# CO2-Ampel_v10.net
KiCad netlist of a schematic drawn in EAGLE
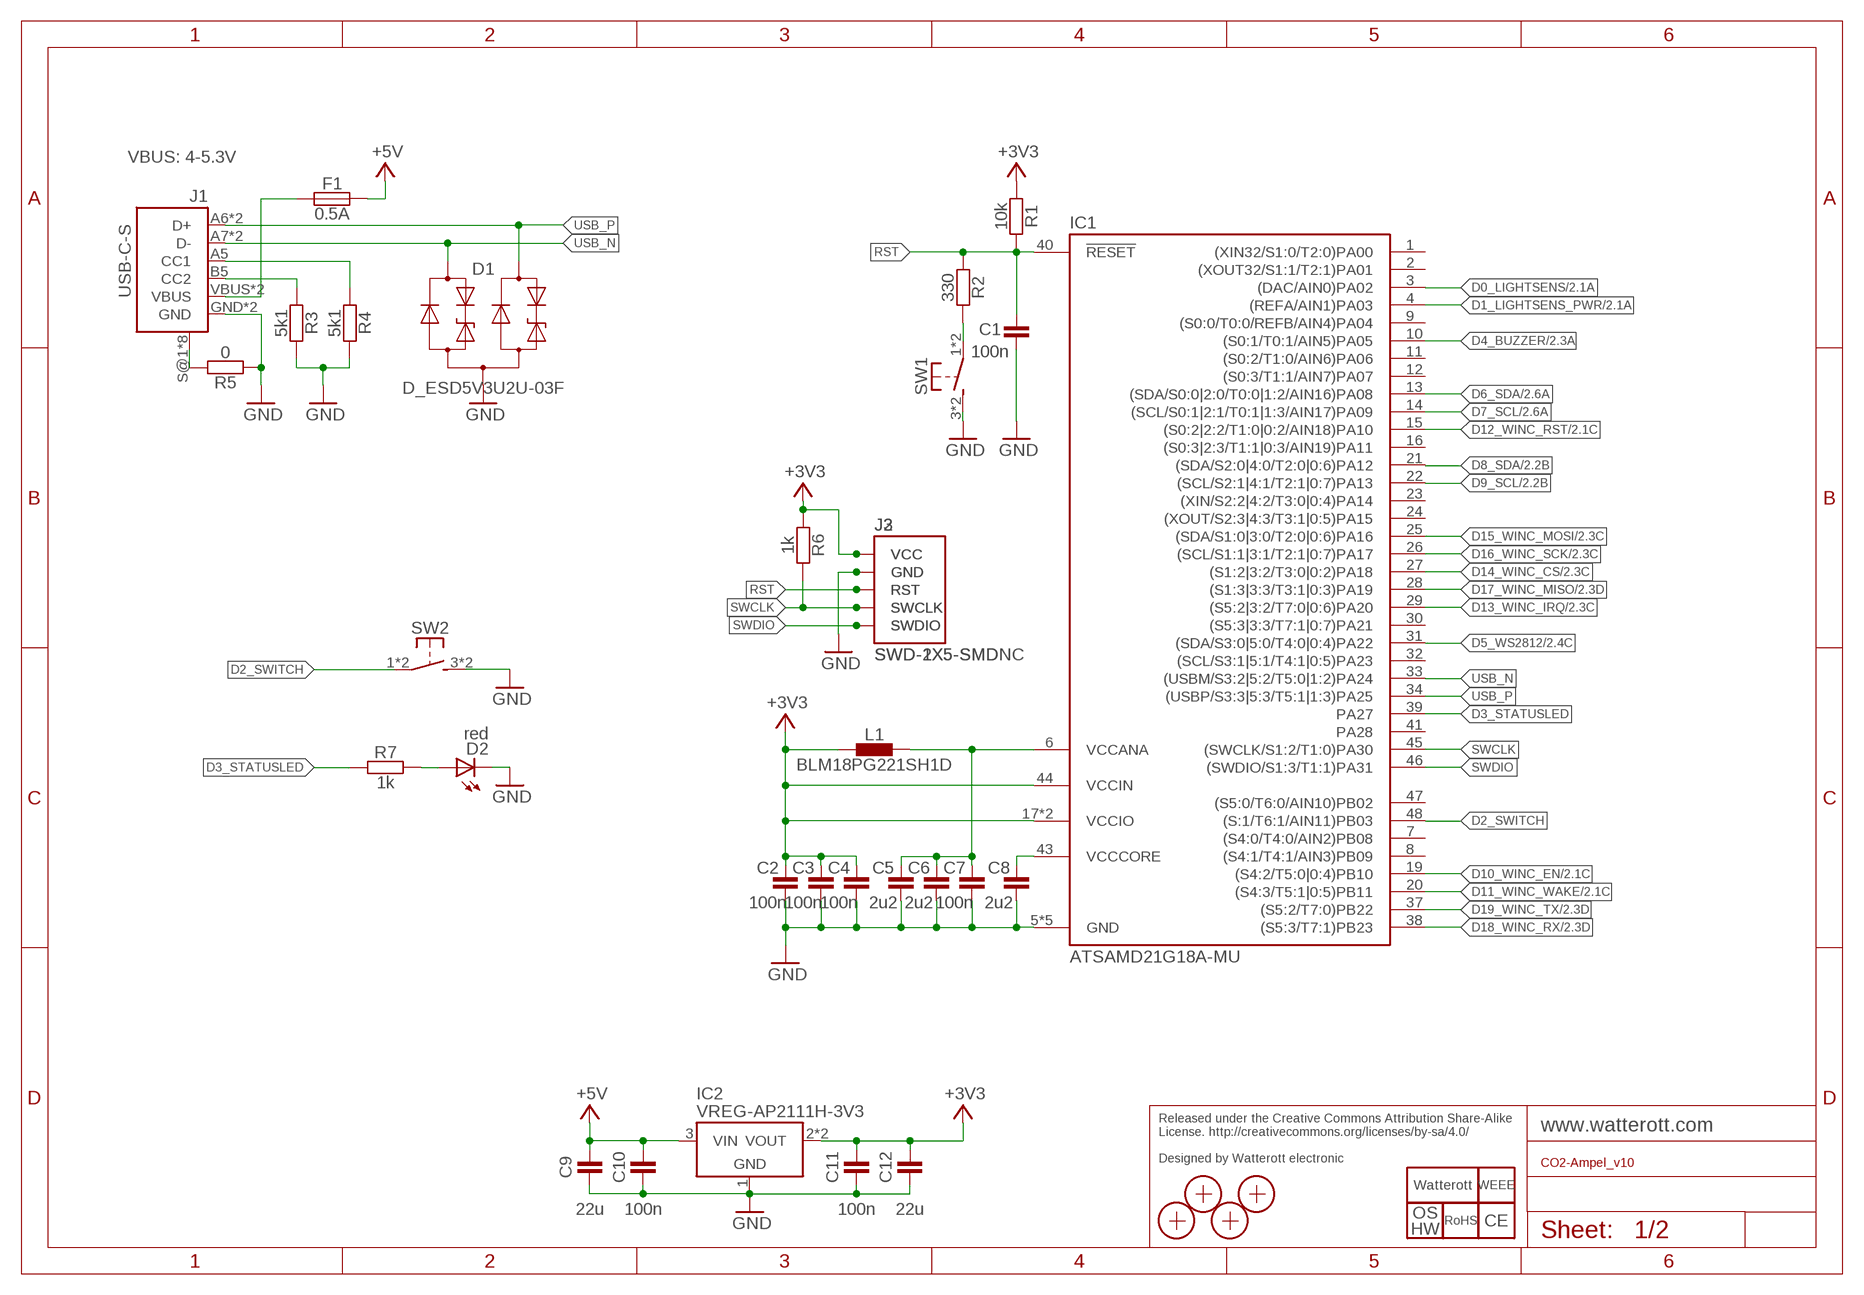
[diagram p0: schematic, sheet 1]
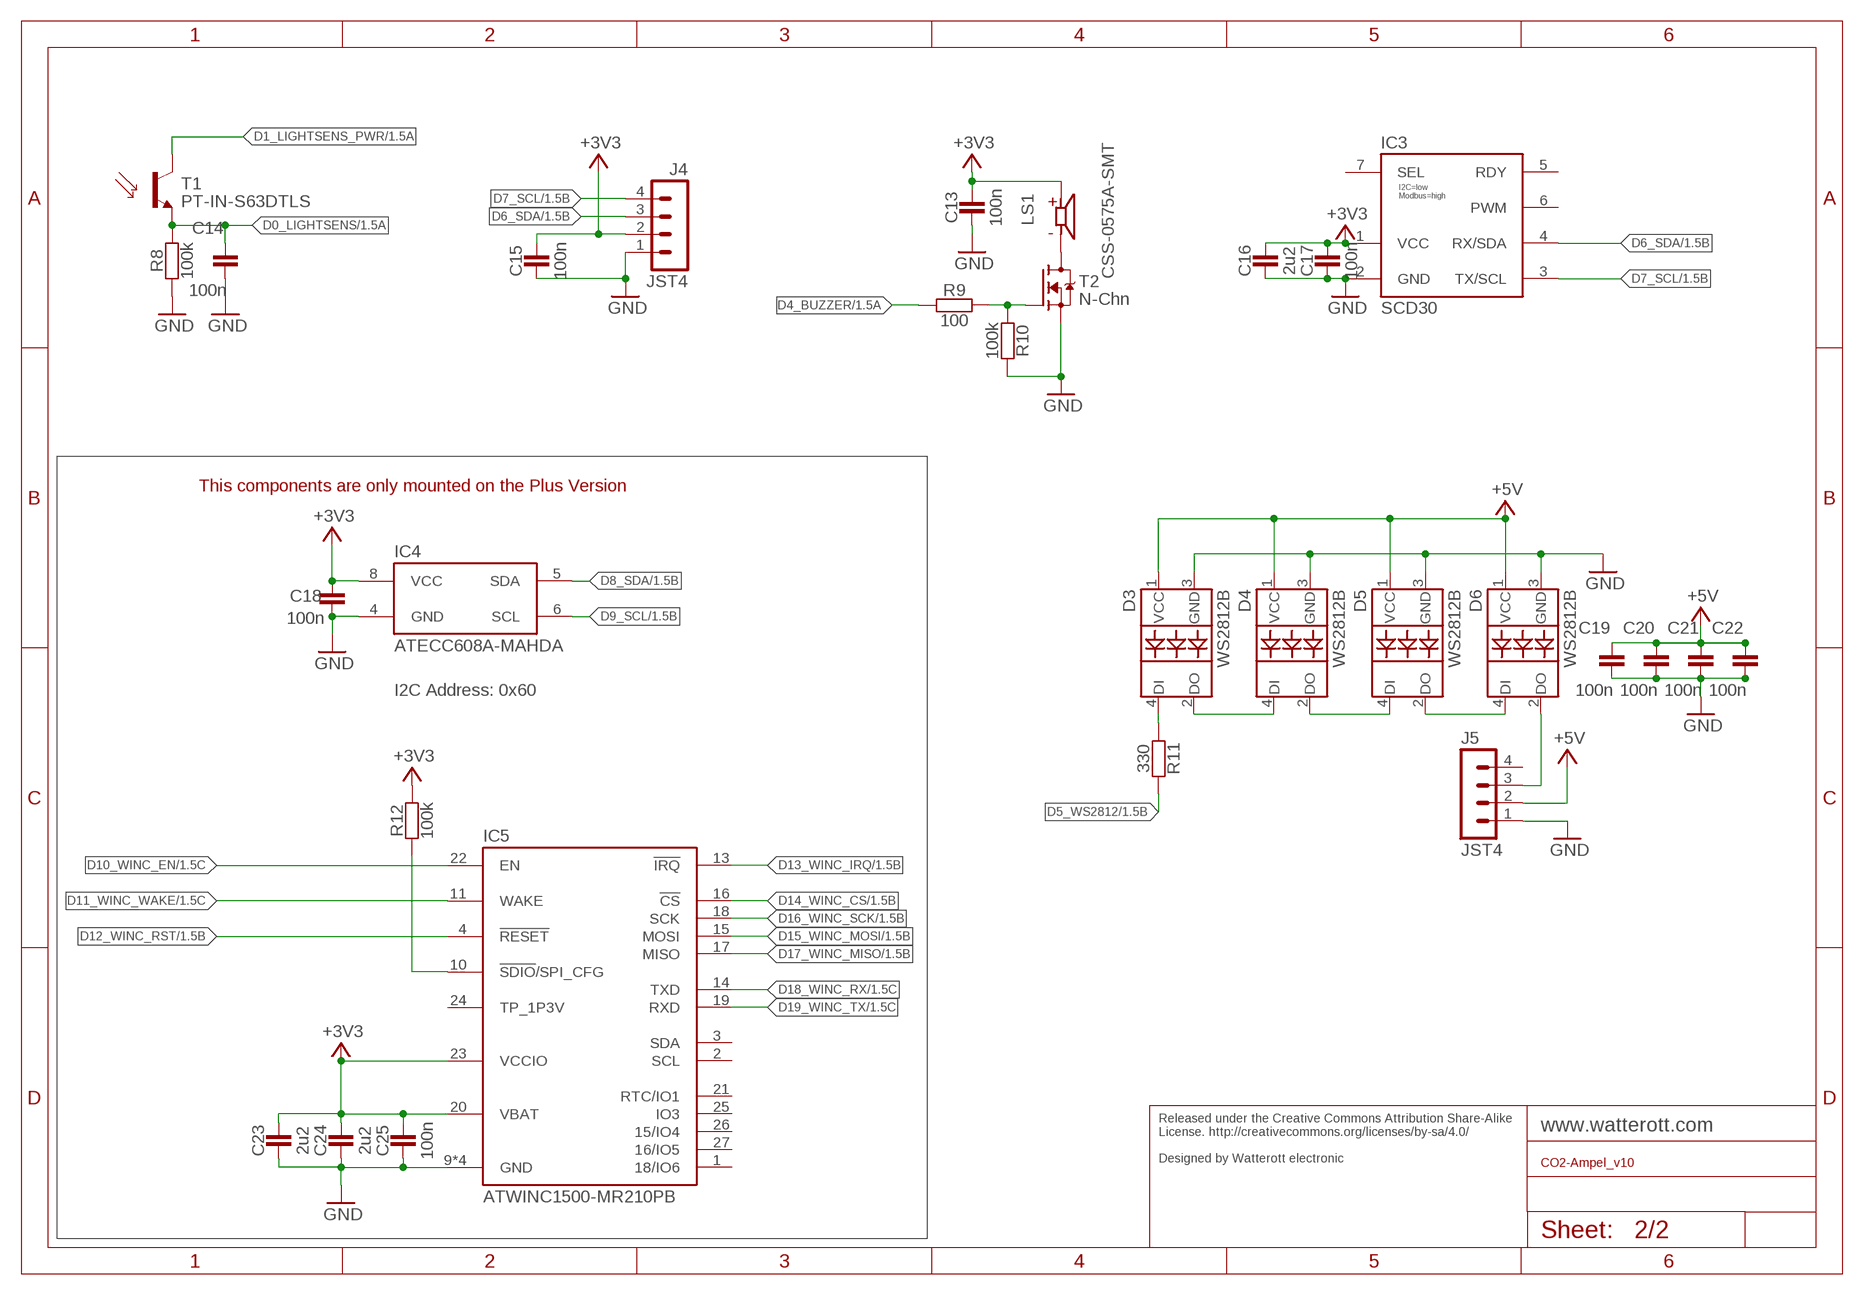
[diagram p1: schematic, sheet 2]

(export (version "E")
  (design (tool "Eeschema 10.0.6"))
  (components
    (comp (ref "C1")
      (value "100n")
      (footprint "eagle-import:C0402")
      (libsource (lib "eagle-import") (part "CAPACITOR-0402"))
    )
    (comp (ref "C2")
      (value "100n")
      (footprint "eagle-import:C0402")
      (libsource (lib "eagle-import") (part "CAPACITOR-0402"))
    )
    (comp (ref "C3")
      (value "100n")
      (footprint "eagle-import:C0402")
      (libsource (lib "eagle-import") (part "CAPACITOR-0402"))
    )
    (comp (ref "C4")
      (value "100n")
      (footprint "eagle-import:C0402")
      (libsource (lib "eagle-import") (part "CAPACITOR-0402"))
    )
    (comp (ref "C5")
      (value "2u2")
      (footprint "eagle-import:C0402")
      (libsource (lib "eagle-import") (part "CAPACITOR-0402"))
    )
    (comp (ref "C6")
      (value "2u2")
      (footprint "eagle-import:C0402")
      (libsource (lib "eagle-import") (part "CAPACITOR-0402"))
    )
    (comp (ref "C7")
      (value "100n")
      (footprint "eagle-import:C0402")
      (libsource (lib "eagle-import") (part "CAPACITOR-0402"))
    )
    (comp (ref "C8")
      (value "2u2")
      (footprint "eagle-import:C0402")
      (libsource (lib "eagle-import") (part "CAPACITOR-0402"))
    )
    (comp (ref "C9")
      (value "22u")
      (footprint "eagle-import:C0805")
      (libsource (lib "eagle-import") (part "CAPACITOR-0805"))
    )
    (comp (ref "C10")
      (value "100n")
      (footprint "eagle-import:C0402")
      (libsource (lib "eagle-import") (part "CAPACITOR-0402"))
    )
    (comp (ref "C11")
      (value "100n")
      (footprint "eagle-import:C0402")
      (libsource (lib "eagle-import") (part "CAPACITOR-0402"))
    )
    (comp (ref "C12")
      (value "22u")
      (footprint "eagle-import:C0805")
      (libsource (lib "eagle-import") (part "CAPACITOR-0805"))
    )
    (comp (ref "D1")
      (value "D_ESD5V3U2U-03F")
      (footprint "eagle-import:SOT723")
      (libsource (lib "eagle-import") (part "D_ESD5V3U2U-03F"))
    )
    (comp (ref "D2")
      (value "red")
      (footprint "eagle-import:C0603")
      (libsource (lib "eagle-import") (part "LED-0603"))
    )
    (comp (ref "F1")
      (value "0.5A")
      (footprint "eagle-import:C0805")
      (libsource (lib "eagle-import") (part "FUSE-0805"))
    )
    (comp (ref "IC1")
      (value "ATSAMD21G18A-MU")
      (footprint "eagle-import:QFN48-PAD")
      (libsource (lib "eagle-import") (part "ATSAMD21G18A-MU"))
    )
    (comp (ref "IC2")
      (value "VREG-AP2111H-3V3")
      (footprint "eagle-import:SOT223")
      (libsource (lib "eagle-import") (part "VREG-TS1117CW-3V3"))
    )
    (comp (ref "J1")
      (value "USB-C-S")
      (footprint "eagle-import:USB-C-S")
      (libsource (lib "eagle-import") (part "USB-C-S"))
    )
    (comp (ref "J2")
      (value "SWD-2X5-SMD")
      (footprint "eagle-import:SWD-2X5_SMD")
      (libsource (lib "eagle-import") (part "SWD-2X5-SMD"))
    )
    (comp (ref "J3")
      (value "SWD-1X5-SMDNC")
      (footprint "eagle-import:SWD-1X5_SMDNC")
      (libsource (lib "eagle-import") (part "SWD-1X5-SMDNC"))
    )
    (comp (ref "L1")
      (value "BLM18PG221SH1D")
      (footprint "eagle-import:C0603")
      (libsource (lib "eagle-import") (part "INDUCTOR-0603"))
    )
    (comp (ref "LOGO1")
      (value "LOGO_SPARK-4")
      (footprint "eagle-import:SPARK_4MM")
      (libsource (lib "eagle-import") (part "LOGO_SPARK-4"))
    )
    (comp (ref "LOGO2")
      (value "LOGO_WEEE-4")
      (footprint "eagle-import:WEEE_4MM")
      (libsource (lib "eagle-import") (part "LOGO_WEEE-4"))
    )
    (comp (ref "LOGO3")
      (value "OSHW_LOGOX0070")
      (footprint "eagle-import:OSHW_3MM")
      (libsource (lib "eagle-import") (part "LOGO_OSHW-3"))
    )
    (comp (ref "LOGO4")
      (value "LOGO_ROHS-4")
      (footprint "eagle-import:ROHS_4MM")
      (libsource (lib "eagle-import") (part "LOGO_ROHS-4"))
    )
    (comp (ref "LOGO5")
      (value "LOGO_CE-4")
      (footprint "eagle-import:CE_4MM")
      (libsource (lib "eagle-import") (part "LOGO_CE-4"))
    )
    (comp (ref "R1")
      (value "10k")
      (footprint "eagle-import:C0402")
      (libsource (lib "eagle-import") (part "RESISTOR-0402"))
    )
    (comp (ref "R2")
      (value "330")
      (footprint "eagle-import:C0402")
      (libsource (lib "eagle-import") (part "RESISTOR-0402"))
    )
    (comp (ref "R3")
      (value "5k1")
      (footprint "eagle-import:C0402")
      (libsource (lib "eagle-import") (part "RESISTOR-0402"))
    )
    (comp (ref "R4")
      (value "5k1")
      (footprint "eagle-import:C0402")
      (libsource (lib "eagle-import") (part "RESISTOR-0402"))
    )
    (comp (ref "R5")
      (value "0")
      (footprint "eagle-import:C0603")
      (libsource (lib "eagle-import") (part "RESISTOR-0603"))
    )
    (comp (ref "R6")
      (value "1k")
      (footprint "eagle-import:C0402")
      (libsource (lib "eagle-import") (part "RESISTOR-0402"))
    )
    (comp (ref "R7")
      (value "1k")
      (footprint "eagle-import:C0402")
      (libsource (lib "eagle-import") (part "RESISTOR-0402"))
    )
    (comp (ref "SW1")
      (value "PTS645SK50SMTR92-Red")
      (footprint "eagle-import:PTS840P")
      (libsource (lib "eagle-import") (part "SW-TACTILE-PTS840P"))
    )
    (comp (ref "SW2")
      (value "PTS645SH50SMTR92-Grey")
      (footprint "eagle-import:PTS840P")
      (libsource (lib "eagle-import") (part "SW-TACTILE-PTS840P"))
    )
    (comp (ref "X1")
      (value "PASSER-07")
      (footprint "eagle-import:PASSER_07MM")
      (libsource (lib "eagle-import") (part "PASSER-07"))
    )
    (comp (ref "X2")
      (value "PASSER-07")
      (footprint "eagle-import:PASSER_07MM")
      (libsource (lib "eagle-import") (part "PASSER-07"))
    )
    (comp (ref "X3")
      (value "PASSER-07")
      (footprint "eagle-import:PASSER_07MM")
      (libsource (lib "eagle-import") (part "PASSER-07"))
    )
    (comp (ref "X4")
      (value "PASSER-07")
      (footprint "eagle-import:PASSER_07MM")
      (libsource (lib "eagle-import") (part "PASSER-07"))
    )
    (comp (ref "C13")
      (value "100n")
      (footprint "eagle-import:C0402")
      (libsource (lib "eagle-import") (part "CAPACITOR-0402"))
    )
    (comp (ref "C14")
      (value "100n")
      (footprint "eagle-import:C0402")
      (libsource (lib "eagle-import") (part "CAPACITOR-0402"))
    )
    (comp (ref "C15")
      (value "100n")
      (footprint "eagle-import:C0402")
      (libsource (lib "eagle-import") (part "CAPACITOR-0402"))
    )
    (comp (ref "C16")
      (value "2u2")
      (footprint "eagle-import:C0402")
      (libsource (lib "eagle-import") (part "CAPACITOR-0402"))
    )
    (comp (ref "C17")
      (value "100n")
      (footprint "eagle-import:C0402")
      (libsource (lib "eagle-import") (part "CAPACITOR-0402"))
    )
    (comp (ref "C18")
      (value "100n")
      (footprint "eagle-import:C0402")
      (libsource (lib "eagle-import") (part "CAPACITOR-0402"))
    )
    (comp (ref "C19")
      (value "100n")
      (footprint "eagle-import:C0402")
      (libsource (lib "eagle-import") (part "CAPACITOR-0402"))
    )
    (comp (ref "C20")
      (value "100n")
      (footprint "eagle-import:C0402")
      (libsource (lib "eagle-import") (part "CAPACITOR-0402"))
    )
    (comp (ref "C21")
      (value "100n")
      (footprint "eagle-import:C0402")
      (libsource (lib "eagle-import") (part "CAPACITOR-0402"))
    )
    (comp (ref "C22")
      (value "100n")
      (footprint "eagle-import:C0402")
      (libsource (lib "eagle-import") (part "CAPACITOR-0402"))
    )
    (comp (ref "C23")
      (value "2u2")
      (footprint "eagle-import:C0402")
      (libsource (lib "eagle-import") (part "CAPACITOR-0402"))
    )
    (comp (ref "C24")
      (value "2u2")
      (footprint "eagle-import:C0402")
      (libsource (lib "eagle-import") (part "CAPACITOR-0402"))
    )
    (comp (ref "C25")
      (value "100n")
      (footprint "eagle-import:C0402")
      (libsource (lib "eagle-import") (part "CAPACITOR-0402"))
    )
    (comp (ref "D3")
      (value "WS2812B")
      (footprint "eagle-import:WS2812B")
      (libsource (lib "eagle-import") (part "WS2812B"))
    )
    (comp (ref "D4")
      (value "WS2812B")
      (footprint "eagle-import:WS2812B")
      (libsource (lib "eagle-import") (part "WS2812B"))
    )
    (comp (ref "D5")
      (value "WS2812B")
      (footprint "eagle-import:WS2812B")
      (libsource (lib "eagle-import") (part "WS2812B"))
    )
    (comp (ref "D6")
      (value "WS2812B")
      (footprint "eagle-import:WS2812B")
      (libsource (lib "eagle-import") (part "WS2812B"))
    )
    (comp (ref "IC3")
      (value "SCD30")
      (footprint "eagle-import:SCD30")
      (libsource (lib "eagle-import") (part "SCD30"))
    )
    (comp (ref "IC4")
      (value "ATECC608A-MAHDA")
      (footprint "eagle-import:UDFN8")
      (libsource (lib "eagle-import") (part "ATECC608A-MAHDA"))
    )
    (comp (ref "IC5")
      (value "ATWINC1500-MR210PB")
      (footprint "eagle-import:ATWINC1500-MX210")
      (libsource (lib "eagle-import") (part "ATWINC1500-MR210PB"))
    )
    (comp (ref "J4")
      (value "JST4")
      (footprint "eagle-import:JST_SM04B-SRSS-TB")
      (libsource (lib "eagle-import") (part "JST4"))
    )
    (comp (ref "J5")
      (value "JST4")
      (footprint "eagle-import:JST_SM04B-SRSS-TB")
      (libsource (lib "eagle-import") (part "JST4"))
    )
    (comp (ref "LS1")
      (value "CSS-0575A-SMT")
      (footprint "eagle-import:CUI_CSS-0575A-SMT")
      (fields (field (name "MF") "CUI"))
      (libsource (lib "eagle-import") (part "CSS-0575A-SMT"))
    )
    (comp (ref "R8")
      (value "100k")
      (footprint "eagle-import:C0402")
      (libsource (lib "eagle-import") (part "RESISTOR-0402"))
    )
    (comp (ref "R9")
      (value "100")
      (footprint "eagle-import:C0402")
      (libsource (lib "eagle-import") (part "RESISTOR-0402"))
    )
    (comp (ref "R10")
      (value "100k")
      (footprint "eagle-import:C0402")
      (libsource (lib "eagle-import") (part "RESISTOR-0402"))
    )
    (comp (ref "R11")
      (value "330")
      (footprint "eagle-import:C0402")
      (libsource (lib "eagle-import") (part "RESISTOR-0402"))
    )
    (comp (ref "R12")
      (value "100k")
      (footprint "eagle-import:C0402")
      (libsource (lib "eagle-import") (part "RESISTOR-0402"))
    )
    (comp (ref "T1")
      (value "PT-IN-S63DTLS")
      (footprint "eagle-import:C0603T")
      (libsource (lib "eagle-import") (part "PT-IN-S63DTLS"))
    )
    (comp (ref "T2")
      (value "N-Chn")
      (footprint "eagle-import:SOT23")
      (libsource (lib "eagle-import") (part "MOSFET-N-SOT23"))
    )
  )
  (nets
    (net (code "1") (name "+3V3") (class "Default")
      (node (ref "C11") (pin "2") (pinfunction "2_2") (pintype "passive"))
      (node (ref "C12") (pin "2") (pinfunction "2_2") (pintype "passive"))
      (node (ref "C13") (pin "2") (pinfunction "2_2") (pintype "passive"))
      (node (ref "C15") (pin "2") (pinfunction "2_2") (pintype "passive"))
      (node (ref "C16") (pin "2") (pinfunction "2_2") (pintype "passive"))
      (node (ref "C17") (pin "2") (pinfunction "2_2") (pintype "passive"))
      (node (ref "C18") (pin "2") (pinfunction "2_2") (pintype "passive"))
      (node (ref "C2") (pin "2") (pinfunction "2_2") (pintype "passive"))
      (node (ref "C23") (pin "2") (pinfunction "2_2") (pintype "passive"))
      (node (ref "C24") (pin "2") (pinfunction "2_2") (pintype "passive"))
      (node (ref "C25") (pin "2") (pinfunction "2_2") (pintype "passive"))
      (node (ref "C3") (pin "2") (pinfunction "2_2") (pintype "passive"))
      (node (ref "C4") (pin "2") (pinfunction "2_2") (pintype "passive"))
      (node (ref "IC1") (pin "17") (pinfunction "VCCIO_17") (pintype "power_in"))
      (node (ref "IC1") (pin "36") (pinfunction "VCCIO_36") (pintype "power_in"))
      (node (ref "IC1") (pin "44") (pinfunction "VCCIN_44") (pintype "power_in"))
      (node (ref "IC2") (pin "2") (pinfunction "VOUT_2") (pintype "power_in"))
      (node (ref "IC2") (pin "4") (pinfunction "VOUT_4") (pintype "power_in"))
      (node (ref "IC3") (pin "1") (pinfunction "VCC_1") (pintype "power_in"))
      (node (ref "IC4") (pin "8") (pinfunction "VCC_8") (pintype "power_in"))
      (node (ref "IC5") (pin "20") (pinfunction "VBAT_20") (pintype "power_in"))
      (node (ref "IC5") (pin "23") (pinfunction "VCCIO_23") (pintype "power_in"))
      (node (ref "J2") (pin "VCC") (pinfunction "VCC_VCC") (pintype "power_in"))
      (node (ref "J3") (pin "1-VCC") (pinfunction "VCC_1-VCC") (pintype "power_in"))
      (node (ref "J4") (pin "2") (pinfunction "2_2") (pintype "passive"))
      (node (ref "L1") (pin "1") (pinfunction "1_1") (pintype "passive"))
      (node (ref "LS1") (pin "1") (pinfunction "P_1") (pintype "passive"))
      (node (ref "R1") (pin "1") (pinfunction "1_1") (pintype "passive"))
      (node (ref "R12") (pin "2") (pinfunction "2_2") (pintype "passive"))
      (node (ref "R6") (pin "1") (pinfunction "1_1") (pintype "passive"))
    )
    (net (code "2") (name "+5V") (class "Default")
      (node (ref "C10") (pin "2") (pinfunction "2_2") (pintype "passive"))
      (node (ref "C19") (pin "2") (pinfunction "2_2") (pintype "passive"))
      (node (ref "C20") (pin "2") (pinfunction "2_2") (pintype "passive"))
      (node (ref "C21") (pin "2") (pinfunction "2_2") (pintype "passive"))
      (node (ref "C22") (pin "2") (pinfunction "2_2") (pintype "passive"))
      (node (ref "C9") (pin "2") (pinfunction "2_2") (pintype "passive"))
      (node (ref "D3") (pin "1") (pinfunction "VCC_1") (pintype "power_in"))
      (node (ref "D4") (pin "1") (pinfunction "VCC_1") (pintype "power_in"))
      (node (ref "D5") (pin "1") (pinfunction "VCC_1") (pintype "power_in"))
      (node (ref "D6") (pin "1") (pinfunction "VCC_1") (pintype "power_in"))
      (node (ref "F1") (pin "2") (pinfunction "2_2") (pintype "passive"))
      (node (ref "IC2") (pin "3") (pinfunction "VIN_3") (pintype "power_in"))
      (node (ref "J5") (pin "2") (pinfunction "2_2") (pintype "passive"))
    )
    (net (code "3") (name "D0_LIGHTSENS") (class "Default")
      (node (ref "C14") (pin "2") (pinfunction "2_2") (pintype "passive"))
      (node (ref "IC1") (pin "3") (pinfunction "(DAC/AIN0)PA02_3") (pintype "bidirectional"))
      (node (ref "R8") (pin "2") (pinfunction "2_2") (pintype "passive"))
      (node (ref "T1") (pin "E") (pinfunction "E_E") (pintype "passive"))
    )
    (net (code "4") (name "D1_LIGHTSENS_PWR") (class "Default")
      (node (ref "IC1") (pin "4") (pinfunction "(REFA/AIN1)PA03_4") (pintype "bidirectional"))
      (node (ref "T1") (pin "C") (pinfunction "C_C") (pintype "passive"))
    )
    (net (code "5") (name "D2_SWITCH") (class "Default")
      (node (ref "IC1") (pin "48") (pinfunction "(S:1/T6:1/AIN11)PB03_48") (pintype "bidirectional"))
      (node (ref "SW2") (pin "1") (pinfunction "P1_1") (pintype "passive"))
      (node (ref "SW2") (pin "2") (pinfunction "P1_2") (pintype "passive"))
    )
    (net (code "6") (name "D3_STATUSLED") (class "Default")
      (node (ref "IC1") (pin "39") (pinfunction "PA27_39") (pintype "bidirectional"))
      (node (ref "R7") (pin "1") (pinfunction "1_1") (pintype "passive"))
    )
    (net (code "7") (name "D4_BUZZER") (class "Default")
      (node (ref "IC1") (pin "10") (pinfunction "(S0:1/T0:1/AIN5)PA05_10") (pintype "bidirectional"))
      (node (ref "R9") (pin "1") (pinfunction "1_1") (pintype "passive"))
    )
    (net (code "8") (name "D5_WS2812") (class "Default")
      (node (ref "IC1") (pin "31") (pinfunction "(SDA/S3:0|5:0/T4:0|0:4)PA22_31") (pintype "bidirectional"))
      (node (ref "R11") (pin "2") (pinfunction "2_2") (pintype "passive"))
    )
    (net (code "9") (name "D6_SDA") (class "Default")
      (node (ref "IC1") (pin "13") (pinfunction "(SDA/S0:0|2:0/T0:0|1:2/AIN16)PA08_13") (pintype "bidirectional"))
      (node (ref "IC3") (pin "4") (pinfunction "RX/SDA_4") (pintype "bidirectional"))
      (node (ref "J4") (pin "3") (pinfunction "3_3") (pintype "passive"))
    )
    (net (code "10") (name "D7_SCL") (class "Default")
      (node (ref "IC1") (pin "14") (pinfunction "(SCL/S0:1|2:1/T0:1|1:3/AIN17)PA09_14") (pintype "bidirectional"))
      (node (ref "IC3") (pin "3") (pinfunction "TX/SCL_3") (pintype "bidirectional"))
      (node (ref "J4") (pin "4") (pinfunction "4_4") (pintype "passive"))
    )
    (net (code "11") (name "D8_SDA") (class "Default")
      (node (ref "IC1") (pin "21") (pinfunction "(SDA/S2:0|4:0/T2:0|0:6)PA12_21") (pintype "bidirectional"))
      (node (ref "IC4") (pin "5") (pinfunction "SDA_5") (pintype "bidirectional"))
    )
    (net (code "12") (name "D9_SCL") (class "Default")
      (node (ref "IC1") (pin "22") (pinfunction "(SCL/S2:1|4:1/T2:1|0:7)PA13_22") (pintype "bidirectional"))
      (node (ref "IC4") (pin "6") (pinfunction "SCL_6") (pintype "bidirectional"))
    )
    (net (code "13") (name "D10_WINC_EN") (class "Default")
      (node (ref "IC1") (pin "19") (pinfunction "(S4:2/T5:0|0:4)PB10_19") (pintype "bidirectional"))
      (node (ref "IC5") (pin "22") (pinfunction "EN_22") (pintype "input"))
    )
    (net (code "14") (name "D11_WINC_WAKE") (class "Default")
      (node (ref "IC1") (pin "20") (pinfunction "(S4:3/T5:1|0:5)PB11_20") (pintype "bidirectional"))
      (node (ref "IC5") (pin "11") (pinfunction "WAKE_11") (pintype "input"))
    )
    (net (code "15") (name "D12_WINC_RST") (class "Default")
      (node (ref "IC1") (pin "15") (pinfunction "(S0:2|2:2/T1:0|0:2/AIN18)PA10_15") (pintype "bidirectional"))
      (node (ref "IC5") (pin "4") (pinfunction "~{RESET}_4") (pintype "input"))
    )
    (net (code "16") (name "D13_WINC_IRQ") (class "Default")
      (node (ref "IC1") (pin "29") (pinfunction "(S5:2|3:2/T7:0|0:6)PA20_29") (pintype "bidirectional"))
      (node (ref "IC5") (pin "13") (pinfunction "~{IRQ}_13") (pintype "output"))
    )
    (net (code "17") (name "D14_WINC_CS") (class "Default")
      (node (ref "IC1") (pin "27") (pinfunction "(S1:2|3:2/T3:0|0:2)PA18_27") (pintype "bidirectional"))
      (node (ref "IC5") (pin "16") (pinfunction "~{CS}_16") (pintype "input"))
    )
    (net (code "18") (name "D15_WINC_MOSI") (class "Default")
      (node (ref "IC1") (pin "25") (pinfunction "(SDA/S1:0|3:0/T2:0|0:6)PA16_25") (pintype "bidirectional"))
      (node (ref "IC5") (pin "15") (pinfunction "MOSI_15") (pintype "input"))
    )
    (net (code "19") (name "D16_WINC_SCK") (class "Default")
      (node (ref "IC1") (pin "26") (pinfunction "(SCL/S1:1|3:1/T2:1|0:7)PA17_26") (pintype "bidirectional"))
      (node (ref "IC5") (pin "18") (pinfunction "SCK_18") (pintype "input"))
    )
    (net (code "20") (name "D17_WINC_MISO") (class "Default")
      (node (ref "IC1") (pin "28") (pinfunction "(S1:3|3:3/T3:1|0:3)PA19_28") (pintype "bidirectional"))
      (node (ref "IC5") (pin "17") (pinfunction "MISO_17") (pintype "output"))
    )
    (net (code "21") (name "D18_WINC_RX") (class "Default")
      (node (ref "IC1") (pin "38") (pinfunction "(S5:3/T7:1)PB23_38") (pintype "bidirectional"))
      (node (ref "IC5") (pin "14") (pinfunction "TXD_14") (pintype "output"))
    )
    (net (code "22") (name "D19_WINC_TX") (class "Default")
      (node (ref "IC1") (pin "37") (pinfunction "(S5:2/T7:0)PB22_37") (pintype "bidirectional"))
      (node (ref "IC5") (pin "19") (pinfunction "RXD_19") (pintype "input"))
    )
    (net (code "23") (name "GND") (class "Default")
      (node (ref "C1") (pin "1") (pinfunction "1_1") (pintype "passive"))
      (node (ref "C10") (pin "1") (pinfunction "1_1") (pintype "passive"))
      (node (ref "C11") (pin "1") (pinfunction "1_1") (pintype "passive"))
      (node (ref "C12") (pin "1") (pinfunction "1_1") (pintype "passive"))
      (node (ref "C13") (pin "1") (pinfunction "1_1") (pintype "passive"))
      (node (ref "C14") (pin "1") (pinfunction "1_1") (pintype "passive"))
      (node (ref "C15") (pin "1") (pinfunction "1_1") (pintype "passive"))
      (node (ref "C16") (pin "1") (pinfunction "1_1") (pintype "passive"))
      (node (ref "C17") (pin "1") (pinfunction "1_1") (pintype "passive"))
      (node (ref "C18") (pin "1") (pinfunction "1_1") (pintype "passive"))
      (node (ref "C19") (pin "1") (pinfunction "1_1") (pintype "passive"))
      (node (ref "C2") (pin "1") (pinfunction "1_1") (pintype "passive"))
      (node (ref "C20") (pin "1") (pinfunction "1_1") (pintype "passive"))
      (node (ref "C21") (pin "1") (pinfunction "1_1") (pintype "passive"))
      (node (ref "C22") (pin "1") (pinfunction "1_1") (pintype "passive"))
      (node (ref "C23") (pin "1") (pinfunction "1_1") (pintype "passive"))
      (node (ref "C24") (pin "1") (pinfunction "1_1") (pintype "passive"))
      (node (ref "C25") (pin "1") (pinfunction "1_1") (pintype "passive"))
      (node (ref "C3") (pin "1") (pinfunction "1_1") (pintype "passive"))
      (node (ref "C4") (pin "1") (pinfunction "1_1") (pintype "passive"))
      (node (ref "C5") (pin "1") (pinfunction "1_1") (pintype "passive"))
      (node (ref "C6") (pin "1") (pinfunction "1_1") (pintype "passive"))
      (node (ref "C7") (pin "1") (pinfunction "1_1") (pintype "passive"))
      (node (ref "C8") (pin "1") (pinfunction "1_1") (pintype "passive"))
      (node (ref "C9") (pin "1") (pinfunction "1_1") (pintype "passive"))
      (node (ref "D1") (pin "3") (pinfunction "A_3") (pintype "passive"))
      (node (ref "D2") (pin "C") (pinfunction "C_C") (pintype "passive"))
      (node (ref "D3") (pin "3") (pinfunction "GND_3") (pintype "power_in"))
      (node (ref "D4") (pin "3") (pinfunction "GND_3") (pintype "power_in"))
      (node (ref "D5") (pin "3") (pinfunction "GND_3") (pintype "power_in"))
      (node (ref "D6") (pin "3") (pinfunction "GND_3") (pintype "power_in"))
      (node (ref "IC1") (pin "18") (pinfunction "GND_18") (pintype "power_in"))
      (node (ref "IC1") (pin "35") (pinfunction "GND_35") (pintype "power_in"))
      (node (ref "IC1") (pin "42") (pinfunction "GND_42") (pintype "power_in"))
      (node (ref "IC1") (pin "5") (pinfunction "GND_5") (pintype "power_in"))
      (node (ref "IC1") (pin "TP") (pinfunction "GND_TP") (pintype "power_in"))
      (node (ref "IC2") (pin "1") (pinfunction "GND_1") (pintype "power_in"))
      (node (ref "IC3") (pin "2") (pinfunction "GND_2") (pintype "power_in"))
      (node (ref "IC4") (pin "4") (pinfunction "GND_4") (pintype "power_in"))
      (node (ref "IC5") (pin "12") (pinfunction "GND_12") (pintype "power_in"))
      (node (ref "IC5") (pin "28") (pinfunction "GND_28") (pintype "power_in"))
      (node (ref "IC5") (pin "9") (pinfunction "GND_9") (pintype "power_in"))
      (node (ref "IC5") (pin "GND") (pinfunction "GND_GND") (pintype "power_in"))
      (node (ref "J1") (pin "GND") (pinfunction "GND_GND") (pintype "power_in"))
      (node (ref "J1") (pin "GND2") (pinfunction "GND_GND2") (pintype "power_in"))
      (node (ref "J2") (pin "GND@1") (pinfunction "GND_GND@1") (pintype "power_in"))
      (node (ref "J2") (pin "GND@2") (pinfunction "GND_GND@2") (pintype "power_in"))
      (node (ref "J2") (pin "GND@3") (pinfunction "GND_GND@3") (pintype "power_in"))
      (node (ref "J3") (pin "2-GND") (pinfunction "GND_2-GND") (pintype "power_in"))
      (node (ref "J4") (pin "1") (pinfunction "1_1") (pintype "passive"))
      (node (ref "J5") (pin "1") (pinfunction "1_1") (pintype "passive"))
      (node (ref "R10") (pin "2") (pinfunction "2_2") (pintype "passive"))
      (node (ref "R3") (pin "2") (pinfunction "2_2") (pintype "passive"))
      (node (ref "R4") (pin "2") (pinfunction "2_2") (pintype "passive"))
      (node (ref "R5") (pin "1") (pinfunction "1_1") (pintype "passive"))
      (node (ref "R8") (pin "1") (pinfunction "1_1") (pintype "passive"))
      (node (ref "SW1") (pin "3") (pinfunction "S1_3") (pintype "passive"))
      (node (ref "SW1") (pin "4") (pinfunction "S1_4") (pintype "passive"))
      (node (ref "SW2") (pin "3") (pinfunction "S1_3") (pintype "passive"))
      (node (ref "SW2") (pin "4") (pinfunction "S1_4") (pintype "passive"))
      (node (ref "T2") (pin "2") (pinfunction "S_2") (pintype "passive"))
    )
    (net (code "24") (name "Net-(D2-PadA)") (class "Default")
      (node (ref "D2") (pin "A") (pinfunction "A_A") (pintype "passive"))
      (node (ref "R7") (pin "2") (pinfunction "2_2") (pintype "passive"))
    )
    (net (code "25") (name "Net-(D3-DI)") (class "Default")
      (node (ref "D3") (pin "4") (pinfunction "DI_4") (pintype "bidirectional"))
      (node (ref "R11") (pin "1") (pinfunction "1_1") (pintype "passive"))
    )
    (net (code "26") (name "Net-(D3-DO)") (class "Default")
      (node (ref "D3") (pin "2") (pinfunction "DO_2") (pintype "bidirectional"))
      (node (ref "D4") (pin "4") (pinfunction "DI_4") (pintype "bidirectional"))
    )
    (net (code "27") (name "Net-(D4-DO)") (class "Default")
      (node (ref "D4") (pin "2") (pinfunction "DO_2") (pintype "bidirectional"))
      (node (ref "D5") (pin "4") (pinfunction "DI_4") (pintype "bidirectional"))
    )
    (net (code "28") (name "Net-(D5-DO)") (class "Default")
      (node (ref "D5") (pin "2") (pinfunction "DO_2") (pintype "bidirectional"))
      (node (ref "D6") (pin "4") (pinfunction "DI_4") (pintype "bidirectional"))
    )
    (net (code "29") (name "Net-(D6-DO)") (class "Default")
      (node (ref "D6") (pin "2") (pinfunction "DO_2") (pintype "bidirectional"))
      (node (ref "J5") (pin "3") (pinfunction "3_3") (pintype "passive"))
    )
    (net (code "30") (name "Net-(F1-Pad1)") (class "Default")
      (node (ref "F1") (pin "1") (pinfunction "1_1") (pintype "passive"))
      (node (ref "J1") (pin "VBUS") (pinfunction "VBUS_VBUS") (pintype "power_in"))
      (node (ref "J1") (pin "VBUS2") (pinfunction "VBUS_VBUS2") (pintype "power_in"))
    )
    (net (code "31") (name "Net-(IC1-VCCANA)") (class "Default")
      (node (ref "C5") (pin "2") (pinfunction "2_2") (pintype "passive"))
      (node (ref "C6") (pin "2") (pinfunction "2_2") (pintype "passive"))
      (node (ref "C7") (pin "2") (pinfunction "2_2") (pintype "passive"))
      (node (ref "IC1") (pin "6") (pinfunction "VCCANA_6") (pintype "power_in"))
      (node (ref "L1") (pin "2") (pinfunction "2_2") (pintype "passive"))
    )
    (net (code "32") (name "Net-(IC1-VCCCORE)") (class "Default")
      (node (ref "C8") (pin "2") (pinfunction "2_2") (pintype "passive"))
      (node (ref "IC1") (pin "43") (pinfunction "VCCCORE_43") (pintype "power_in"))
    )
    (net (code "33") (name "Net-(IC5-~{SDIO}{slash}SPI_CFG)") (class "Default")
      (node (ref "IC5") (pin "10") (pinfunction "~{SDIO}/SPI_CFG_10") (pintype "input"))
      (node (ref "R12") (pin "1") (pinfunction "1_1") (pintype "passive"))
    )
    (net (code "34") (name "Net-(J1-CC1)") (class "Default")
      (node (ref "J1") (pin "A5") (pinfunction "CC1_A5") (pintype "bidirectional"))
      (node (ref "R4") (pin "1") (pinfunction "1_1") (pintype "passive"))
    )
    (net (code "35") (name "Net-(J1-CC2)") (class "Default")
      (node (ref "J1") (pin "B5") (pinfunction "CC2_B5") (pintype "bidirectional"))
      (node (ref "R3") (pin "1") (pinfunction "1_1") (pintype "passive"))
    )
    (net (code "36") (name "Net-(J1-SHIELD-PadS@1)") (class "Default")
      (node (ref "J1") (pin "S@1") (pinfunction "SHIELD_S@1") (pintype "passive"))
      (node (ref "J1") (pin "S@2") (pinfunction "SHIELD_S@2") (pintype "passive"))
      (node (ref "J1") (pin "S@3") (pinfunction "SHIELD_S@3") (pintype "passive"))
      (node (ref "J1") (pin "S@4") (pinfunction "SHIELD_S@4") (pintype "passive"))
      (node (ref "J1") (pin "S@5") (pinfunction "SHIELD_S@5") (pintype "passive"))
      (node (ref "J1") (pin "S@6") (pinfunction "SHIELD_S@6") (pintype "passive"))
      (node (ref "J1") (pin "S@7") (pinfunction "SHIELD_S@7") (pintype "passive"))
      (node (ref "J1") (pin "S@8") (pinfunction "SHIELD_S@8") (pintype "passive"))
      (node (ref "R5") (pin "2") (pinfunction "2_2") (pintype "passive"))
    )
    (net (code "37") (name "Net-(LS1-N)") (class "Default")
      (node (ref "LS1") (pin "2") (pinfunction "N_2") (pintype "passive"))
      (node (ref "T2") (pin "3") (pinfunction "D_3") (pintype "passive"))
    )
    (net (code "38") (name "Net-(R2-Pad2)") (class "Default")
      (node (ref "R2") (pin "2") (pinfunction "2_2") (pintype "passive"))
      (node (ref "SW1") (pin "1") (pinfunction "P1_1") (pintype "passive"))
      (node (ref "SW1") (pin "2") (pinfunction "P1_2") (pintype "passive"))
    )
    (net (code "39") (name "Net-(T2-G)") (class "Default")
      (node (ref "R10") (pin "1") (pinfunction "1_1") (pintype "passive"))
      (node (ref "R9") (pin "2") (pinfunction "2_2") (pintype "passive"))
      (node (ref "T2") (pin "1") (pinfunction "G_1") (pintype "passive"))
    )
    (net (code "40") (name "RST") (class "Default")
      (node (ref "C1") (pin "2") (pinfunction "2_2") (pintype "passive"))
      (node (ref "IC1") (pin "40") (pinfunction "~{RESET}_40") (pintype "input"))
      (node (ref "J2") (pin "RST") (pinfunction "RST_RST") (pintype "bidirectional"))
      (node (ref "J3") (pin "3-RST") (pinfunction "RST_3-RST") (pintype "bidirectional"))
      (node (ref "R1") (pin "2") (pinfunction "2_2") (pintype "passive"))
      (node (ref "R2") (pin "1") (pinfunction "1_1") (pintype "passive"))
    )
    (net (code "41") (name "SWCLK") (class "Default")
      (node (ref "IC1") (pin "45") (pinfunction "(SWCLK/S1:2/T1:0)PA30_45") (pintype "bidirectional"))
      (node (ref "J2") (pin "SWCLK") (pinfunction "SWCLK_SWCLK") (pintype "bidirectional"))
      (node (ref "J3") (pin "4-SWDCLK") (pinfunction "SWCLK_4-SWDCLK") (pintype "bidirectional"))
      (node (ref "R6") (pin "2") (pinfunction "2_2") (pintype "passive"))
    )
    (net (code "42") (name "SWDIO") (class "Default")
      (node (ref "IC1") (pin "46") (pinfunction "(SWDIO/S1:3/T1:1)PA31_46") (pintype "bidirectional"))
      (node (ref "J2") (pin "SWDIO") (pinfunction "SWDIO_SWDIO") (pintype "bidirectional"))
      (node (ref "J3") (pin "5-SWDIO") (pinfunction "SWDIO_5-SWDIO") (pintype "bidirectional"))
    )
    (net (code "43") (name "USB_N") (class "Default")
      (node (ref "D1") (pin "1") (pinfunction "C1_1") (pintype "passive"))
      (node (ref "IC1") (pin "33") (pinfunction "(USBM/S3:2|5:2/T5:0|1:2)PA24_33") (pintype "bidirectional"))
      (node (ref "J1") (pin "A7") (pinfunction "D-_A7") (pintype "bidirectional"))
      (node (ref "J1") (pin "B7") (pinfunction "D-_B7") (pintype "bidirectional"))
    )
    (net (code "44") (name "USB_P") (class "Default")
      (node (ref "D1") (pin "2") (pinfunction "C2_2") (pintype "passive"))
      (node (ref "IC1") (pin "34") (pinfunction "(USBP/S3:3|5:3/T5:1|1:3)PA25_34") (pintype "bidirectional"))
      (node (ref "J1") (pin "A6") (pinfunction "D+_A6") (pintype "bidirectional"))
      (node (ref "J1") (pin "B6") (pinfunction "D+_B6") (pintype "bidirectional"))
    )
    (net (code "45") (name "unconnected-(IC1-(S0:0{slash}T0:0{slash}REFB{slash}AIN4)PA04-Pad9)") (class "Default")
      (node (ref "IC1") (pin "9") (pinfunction "(S0:0/T0:0/REFB/AIN4)PA04_9") (pintype "bidirectional"))
    )
    (net (code "46") (name "unconnected-(IC1-(S0:2{slash}T1:0{slash}AIN6)PA06-Pad11)") (class "Default")
      (node (ref "IC1") (pin "11") (pinfunction "(S0:2/T1:0/AIN6)PA06_11") (pintype "bidirectional"))
    )
    (net (code "47") (name "unconnected-(IC1-(S0:3{slash}T1:1{slash}AIN7)PA07-Pad12)") (class "Default")
      (node (ref "IC1") (pin "12") (pinfunction "(S0:3/T1:1/AIN7)PA07_12") (pintype "bidirectional"))
    )
    (net (code "48") (name "unconnected-(IC1-(S0:3|2:3{slash}T1:1|0:3{slash}AIN19)PA11-Pad16)") (class "Default")
      (node (ref "IC1") (pin "16") (pinfunction "(S0:3|2:3/T1:1|0:3/AIN19)PA11_16") (pintype "bidirectional"))
    )
    (net (code "49") (name "unconnected-(IC1-(S4:0{slash}T4:0{slash}AIN2)PB08-Pad7)") (class "Default")
      (node (ref "IC1") (pin "7") (pinfunction "(S4:0/T4:0/AIN2)PB08_7") (pintype "bidirectional"))
    )
    (net (code "50") (name "unconnected-(IC1-(S4:1{slash}T4:1{slash}AIN3)PB09-Pad8)") (class "Default")
      (node (ref "IC1") (pin "8") (pinfunction "(S4:1/T4:1/AIN3)PB09_8") (pintype "bidirectional"))
    )
    (net (code "51") (name "unconnected-(IC1-(S5:0{slash}T6:0{slash}AIN10)PB02-Pad47)") (class "Default")
      (node (ref "IC1") (pin "47") (pinfunction "(S5:0/T6:0/AIN10)PB02_47") (pintype "bidirectional"))
    )
    (net (code "52") (name "unconnected-(IC1-(S5:3|3:3{slash}T7:1|0:7)PA21-Pad30)") (class "Default")
      (node (ref "IC1") (pin "30") (pinfunction "(S5:3|3:3/T7:1|0:7)PA21_30") (pintype "bidirectional"))
    )
    (net (code "53") (name "unconnected-(IC1-(SCL{slash}S3:1|5:1{slash}T4:1|0:5)PA23-Pad32)") (class "Default")
      (node (ref "IC1") (pin "32") (pinfunction "(SCL/S3:1|5:1/T4:1|0:5)PA23_32") (pintype "bidirectional"))
    )
    (net (code "54") (name "unconnected-(IC1-(XIN32{slash}S1:0{slash}T2:0)PA00-Pad1)") (class "Default")
      (node (ref "IC1") (pin "1") (pinfunction "(XIN32/S1:0/T2:0)PA00_1") (pintype "bidirectional"))
    )
    (net (code "55") (name "unconnected-(IC1-(XIN{slash}S2:2|4:2{slash}T3:0|0:4)PA14-Pad23)") (class "Default")
      (node (ref "IC1") (pin "23") (pinfunction "(XIN/S2:2|4:2/T3:0|0:4)PA14_23") (pintype "bidirectional"))
    )
    (net (code "56") (name "unconnected-(IC1-(XOUT32{slash}S1:1{slash}T2:1)PA01-Pad2)") (class "Default")
      (node (ref "IC1") (pin "2") (pinfunction "(XOUT32/S1:1/T2:1)PA01_2") (pintype "bidirectional"))
    )
    (net (code "57") (name "unconnected-(IC1-(XOUT{slash}S2:3|4:3{slash}T3:1|0:5)PA15-Pad24)") (class "Default")
      (node (ref "IC1") (pin "24") (pinfunction "(XOUT/S2:3|4:3/T3:1|0:5)PA15_24") (pintype "bidirectional"))
    )
    (net (code "58") (name "unconnected-(IC1-PA28-Pad41)") (class "Default")
      (node (ref "IC1") (pin "41") (pinfunction "PA28_41") (pintype "bidirectional"))
    )
    (net (code "59") (name "unconnected-(IC3-PWM-Pad6)") (class "Default")
      (node (ref "IC3") (pin "6") (pinfunction "PWM_6") (pintype "output"))
    )
    (net (code "60") (name "unconnected-(IC3-RDY-Pad5)") (class "Default")
      (node (ref "IC3") (pin "5") (pinfunction "RDY_5") (pintype "output"))
    )
    (net (code "61") (name "unconnected-(IC3-SEL-Pad7)") (class "Default")
      (node (ref "IC3") (pin "7") (pinfunction "SEL_7") (pintype "bidirectional"))
    )
    (net (code "62") (name "unconnected-(IC5-15{slash}IO4-Pad26)") (class "Default")
      (node (ref "IC5") (pin "26") (pinfunction "15/IO4_26") (pintype "bidirectional"))
    )
    (net (code "63") (name "unconnected-(IC5-16{slash}IO5-Pad27)") (class "Default")
      (node (ref "IC5") (pin "27") (pinfunction "16/IO5_27") (pintype "bidirectional"))
    )
    (net (code "64") (name "unconnected-(IC5-18{slash}IO6-Pad1)") (class "Default")
      (node (ref "IC5") (pin "1") (pinfunction "18/IO6_1") (pintype "bidirectional"))
    )
    (net (code "65") (name "unconnected-(IC5-IO3-Pad25)") (class "Default")
      (node (ref "IC5") (pin "25") (pinfunction "IO3_25") (pintype "bidirectional"))
    )
    (net (code "66") (name "unconnected-(IC5-RTC{slash}IO1-Pad21)") (class "Default")
      (node (ref "IC5") (pin "21") (pinfunction "RTC/IO1_21") (pintype "bidirectional"))
    )
    (net (code "67") (name "unconnected-(IC5-SCL-Pad2)") (class "Default")
      (node (ref "IC5") (pin "2") (pinfunction "SCL_2") (pintype "bidirectional"))
    )
    (net (code "68") (name "unconnected-(IC5-SDA-Pad3)") (class "Default")
      (node (ref "IC5") (pin "3") (pinfunction "SDA_3") (pintype "bidirectional"))
    )
    (net (code "69") (name "unconnected-(IC5-TP_1P3V-Pad24)") (class "Default")
      (node (ref "IC5") (pin "24") (pinfunction "TP_1P3V_24") (pintype "bidirectional"))
    )
    (net (code "70") (name "unconnected-(J5-Pad4)") (class "Default")
      (node (ref "J5") (pin "4") (pinfunction "4_4") (pintype "passive"))
    )
  )
)
